# ESP32.net
KiCad netlist of a schematic drawn in Altium Designer
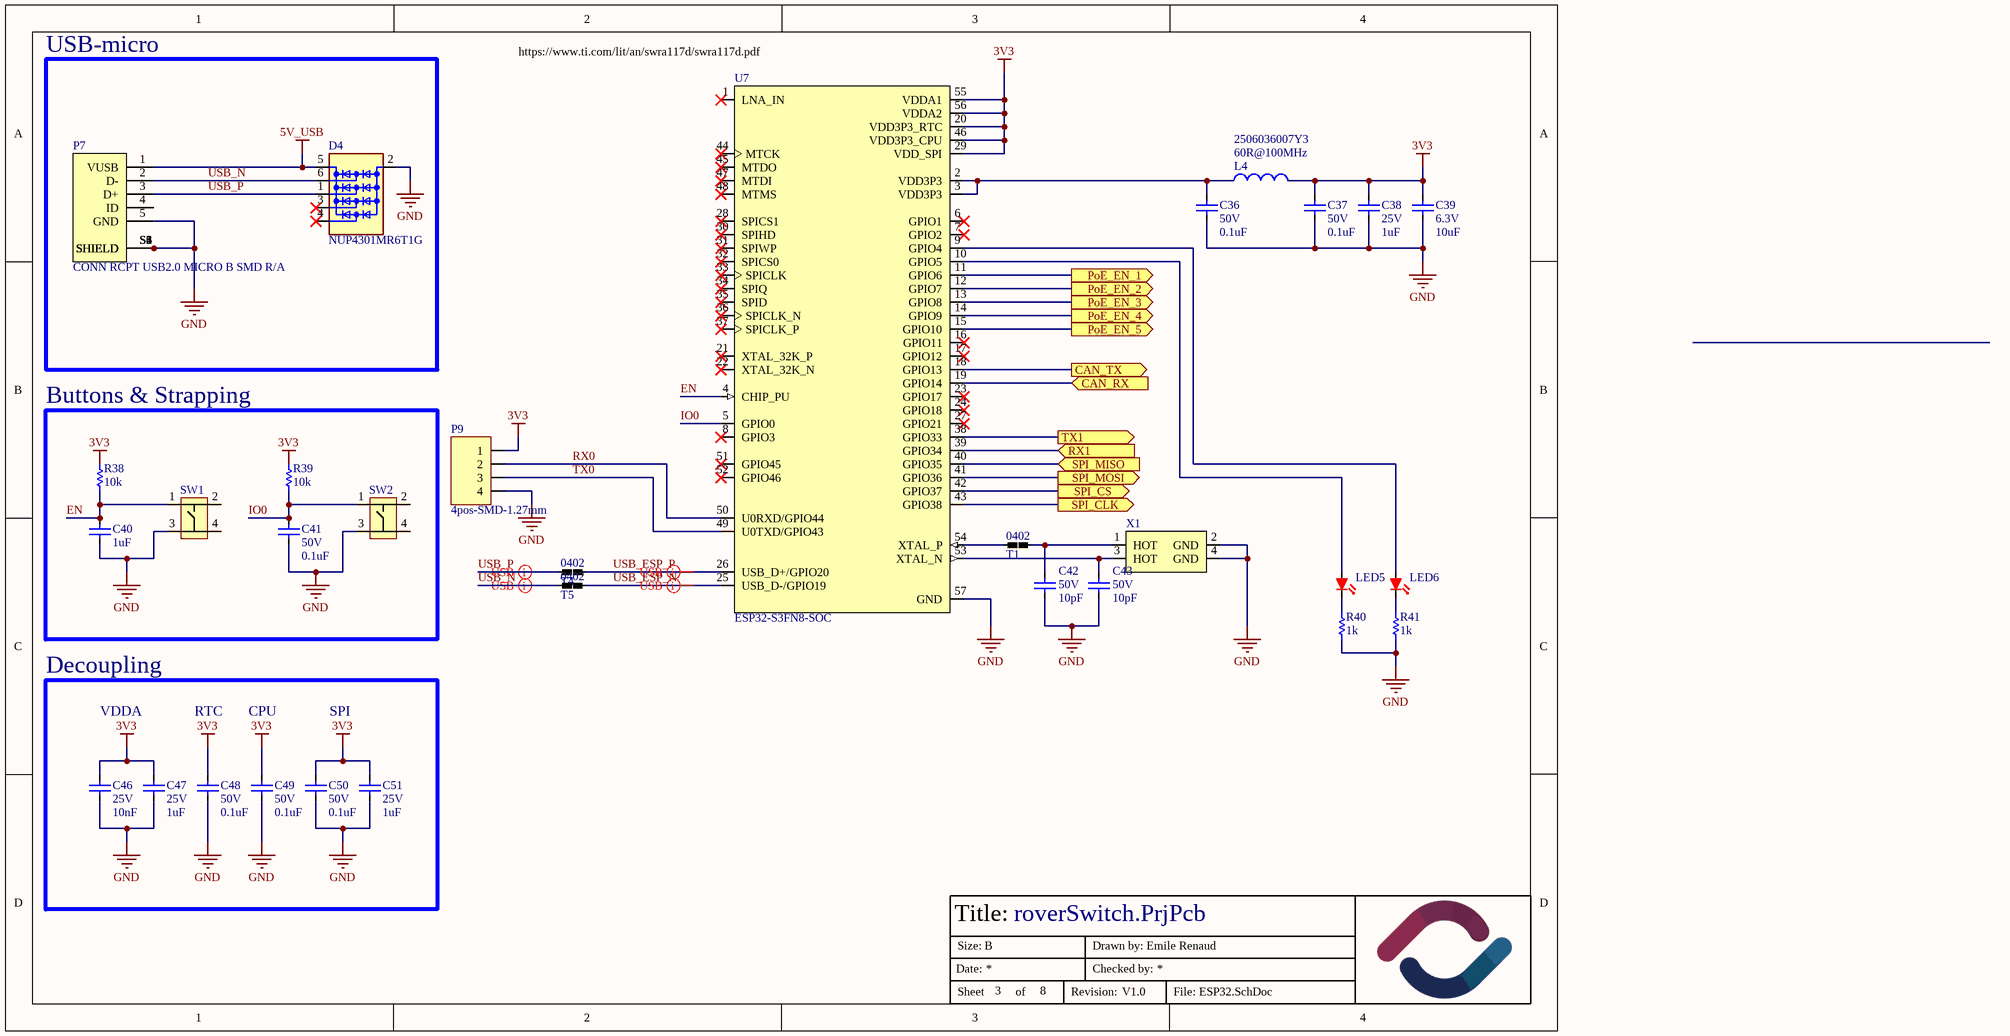
[diagram p0: ESP32.SchDoc]

(export (version "E")
  (design (tool "Eeschema 10.0.6"))
  (components
    (comp (ref "C36")
      (value "0.1uF")
      (footprint "CAPACITOR-0603")
      (description "Capacitor-0603-0.1uF-50V-X7R")
      (fields (field (name "VOLT") "50V"))
      (libsource (lib "Capacitors") (part "Capacitor-0603-0.1uF-50V-X7R"))
    )
    (comp (ref "C37")
      (value "0.1uF")
      (footprint "CAPACITOR-0603")
      (description "Capacitor-0603-0.1uF-50V-X7R")
      (fields (field (name "VOLT") "50V"))
      (libsource (lib "Capacitors") (part "Capacitor-0603-0.1uF-50V-X7R"))
    )
    (comp (ref "C38")
      (value "1uF")
      (footprint "CAPACITOR-0603")
      (description "Capacitor-0603-1uF-25V-X5R")
      (fields (field (name "VOLT") "25V"))
      (libsource (lib "Capacitors") (part "Capacitor-0603-1uF-25V-X5R"))
    )
    (comp (ref "C39")
      (value "10uF")
      (footprint "CAPACITOR-0603")
      (description "Capacitor-0603-10uF-6.3V-X5R, Low ESR, Low ESL")
      (fields (field (name "VOLT") "6.3V") (field (name "Comment") "Capacitor-0603-10uF-6.3V-X5R"))
      (libsource (lib "Capacitors") (part "Capacitor-0603-10uF-6.3V-X5R"))
    )
    (comp (ref "C40")
      (value "1uF")
      (footprint "CAPACITOR-0603")
      (description "Capacitor-0603-1uF-25V-X5R")
      (libsource (lib "Capacitors") (part "Capacitor-0603-1uF-25V-X5R"))
    )
    (comp (ref "C41")
      (value "0.1uF")
      (footprint "CAPACITOR-0603")
      (description "Capacitor-0603-0.1uF-50V-X7R")
      (fields (field (name "VOLT") "50V"))
      (libsource (lib "Capacitors") (part "Capacitor-0603-0.1uF-50V-X7R"))
    )
    (comp (ref "C42")
      (value "10pF")
      (footprint "CAPACITOR-0402")
      (description "Capacitor-0402-10pF-50V-C0G")
      (fields (field (name "VOLT") "50V"))
      (libsource (lib "Capacitors") (part "Capacitor-0402-10pF-50V-C0G"))
    )
    (comp (ref "C43")
      (value "10pF")
      (footprint "CAPACITOR-0402")
      (description "Capacitor-0402-10pF-50V-C0G")
      (fields (field (name "VOLT") "50V"))
      (libsource (lib "Capacitors") (part "Capacitor-0402-10pF-50V-C0G"))
    )
    (comp (ref "C46")
      (value "10nF")
      (footprint "CAPACITOR-0603")
      (description "10000 pF ±10% 25V Ceramic Capacitor X5R 0603 (1608 Metric)")
      (fields (field (name "VOLT") "25V") (field (name "Comment") "Capacitor-0603-10nF-25V-X5R"))
      (libsource (lib "Capacitors") (part "Capacitor-0603-10nF-25V-X5R"))
    )
    (comp (ref "C47")
      (value "1uF")
      (footprint "CAPACITOR-0603")
      (description "Capacitor-0603-1uF-25V-X5R")
      (fields (field (name "VOLT") "25V"))
      (libsource (lib "Capacitors") (part "Capacitor-0603-1uF-25V-X5R"))
    )
    (comp (ref "C48")
      (value "0.1uF")
      (footprint "CAPACITOR-0603")
      (description "Capacitor-0603-0.1uF-50V-X7R")
      (fields (field (name "VOLT") "50V"))
      (libsource (lib "Capacitors") (part "Capacitor-0603-0.1uF-50V-X7R"))
    )
    (comp (ref "C49")
      (value "0.1uF")
      (footprint "CAPACITOR-0603")
      (description "Capacitor-0603-0.1uF-50V-X7R")
      (fields (field (name "VOLT") "50V"))
      (libsource (lib "Capacitors") (part "Capacitor-0603-0.1uF-50V-X7R"))
    )
    (comp (ref "C50")
      (value "0.1uF")
      (footprint "CAPACITOR-0603")
      (description "Capacitor-0603-0.1uF-50V-X7R")
      (fields (field (name "VOLT") "50V"))
      (libsource (lib "Capacitors") (part "Capacitor-0603-0.1uF-50V-X7R"))
    )
    (comp (ref "C51")
      (value "1uF")
      (footprint "CAPACITOR-0603")
      (description "Capacitor-0603-1uF-25V-X5R")
      (fields (field (name "VOLT") "25V"))
      (libsource (lib "Capacitors") (part "Capacitor-0603-1uF-25V-X5R"))
    )
    (comp (ref "D4")
      (value "NUP4301MR6T1G")
      (footprint "SOT-23-6")
      (description "4CH Clamp Ipp Tvs Diode Surface Mount SOT23-6 (SC74)")
      (libsource (lib "diodes") (part "NUP4301MR6T1G"))
    )
    (comp (ref "L4")
      (value "2506036007Y3")
      (footprint "CAPACITOR-0603")
      (description "60 Ohms @ 100 MHz 1 Signal Line Ferrite Bead 0603 (1608 Metric) 3A 40mOhm")
      (fields (field (name "ALTIUM_VALUE") "60R@100MHz"))
      (libsource (lib "Inductors") (part "2506036007Y3"))
    )
    (comp (ref "LED5")
      (value "B1911USD-20D000114U1930")
      (footprint "LED-0603-2PIN")
      (description "LED RED CLEAR 1608 SMD")
      (libsource (lib "LEDs") (part "B1911USD-20D000114U1930"))
    )
    (comp (ref "LED6")
      (value "B1911USD-20D000114U1930")
      (footprint "LED-0603-2PIN")
      (description "LED RED CLEAR 1608 SMD")
      (libsource (lib "LEDs") (part "B1911USD-20D000114U1930"))
    )
    (comp (ref "P7")
      (value "CONN RCPT USB2.0 MICRO B SMD R/A")
      (footprint "FCI_10118193-0001LF")
      (description "USB - micro B USB 2.0 Receptacle Connector 5 Position Surface Mount, Right Angle; Through Hole")
      (libsource (lib "PC-connector") (part "USB-Micro"))
    )
    (comp (ref "P9")
      (value "4pos-SMD-1.27mm")
      (footprint "HDR1X4-SMD-50mils")
      (description "4pos SMD 1.27mm")
      (libsource (lib "Header") (part "4pos-SMD-1.27mm"))
    )
    (comp (ref "R38")
      (value "10k")
      (footprint "Resistor-0603")
      (description "Resistor0603-10k")
      (fields (field (name "Comment") "SMT resistor"))
      (libsource (lib "Resistors") (part "Resistor0603-10k"))
    )
    (comp (ref "R39")
      (value "10k")
      (footprint "Resistor-0603")
      (description "Resistor0603-10k")
      (fields (field (name "Comment") "SMT resistor"))
      (libsource (lib "Resistors") (part "Resistor0603-10k"))
    )
    (comp (ref "R40")
      (value "1k")
      (footprint "Resistor-0603")
      (description "Resistor0603-1k")
      (fields (field (name "Comment") "SMT resistor"))
      (libsource (lib "Resistors") (part "Resistor-0603-1k"))
    )
    (comp (ref "R41")
      (value "1k")
      (footprint "Resistor-0603")
      (description "Resistor0603-1k")
      (fields (field (name "Comment") "SMT resistor"))
      (libsource (lib "Resistors") (part "Resistor-0603-1k"))
    )
    (comp (ref "SW1")
      (value "PTS815 SJM 250 SMTR LFS")
      (footprint "SW4_PTS815 SJM 250 SMTR LFS_CNK")
      (description "TACT 4.2 X 3.2, 2.5 MM H, 180GF,")
      (libsource (lib "THTPushButtonSwitches") (part "PTS815 SJM 250 SMTR LFS"))
    )
    (comp (ref "SW2")
      (value "PTS815 SJM 250 SMTR LFS")
      (footprint "SW4_PTS815 SJM 250 SMTR LFS_CNK")
      (description "TACT 4.2 X 3.2, 2.5 MM H, 180GF,")
      (libsource (lib "THTPushButtonSwitches") (part "PTS815 SJM 250 SMTR LFS"))
    )
    (comp (ref "T1")
      (value "NetTie_0402")
      (footprint "NetTie-0402")
      (libsource (lib "JumpersAndHoles") (part "NetTie_0402"))
    )
    (comp (ref "T4")
      (value "NetTie_0402")
      (footprint "NetTie-0402")
      (libsource (lib "JumpersAndHoles") (part "NetTie_0402"))
    )
    (comp (ref "T5")
      (value "NetTie_0402")
      (footprint "NetTie-0402")
      (libsource (lib "JumpersAndHoles") (part "NetTie_0402"))
    )
    (comp (ref "U7")
      (value "ESP32-S3FN8-SOC")
      (footprint "VFQFN-56 Exposed Pad")
      (fields (field (name "MF") "Espressif Systems") (field (name "MP") "ESP32-S3FN8"))
      (libsource (lib "Microcontrollers") (part "ESP32-S3FN8-SOC"))
    )
    (comp (ref "X1")
      (value "CX2016DB40000D0FLJCC")
      (footprint "4-SMD")
      (description "40 MHz ±10ppm Crystal 8pF 50 Ohms 4-SMD, No Lead")
      (libsource (lib "Crystals") (part "CX2016DB40000D0FLJCC"))
    )
  )
  (nets
    (net (code "1") (name "/CAN_RX") (class "Default")
      (node (ref "U7") (pin "19") (pinfunction "GPIO14_19") (pintype "bidirectional"))
    )
    (net (code "2") (name "/CAN_TX") (class "Default")
      (node (ref "U7") (pin "18") (pinfunction "GPIO13_18") (pintype "bidirectional"))
    )
    (net (code "3") (name "/EN") (class "Default")
      (node (ref "C40") (pin "2") (pinfunction "2_2") (pintype "passive"))
      (node (ref "R38") (pin "1") (pinfunction "1_1") (pintype "passive"))
      (node (ref "SW1") (pin "1") (pinfunction "1_1") (pintype "passive"))
      (node (ref "U7") (pin "4") (pinfunction "CHIP_PU_4") (pintype "input"))
    )
    (net (code "4") (name "/IO0") (class "Default")
      (node (ref "C41") (pin "2") (pinfunction "2_2") (pintype "passive"))
      (node (ref "R39") (pin "1") (pinfunction "1_1") (pintype "passive"))
      (node (ref "SW2") (pin "1") (pinfunction "1_1") (pintype "passive"))
      (node (ref "U7") (pin "5") (pinfunction "GPIO0_5") (pintype "bidirectional"))
    )
    (net (code "5") (name "/PoE_EN_1") (class "Default")
      (node (ref "U7") (pin "11") (pinfunction "GPIO6_11") (pintype "bidirectional"))
    )
    (net (code "6") (name "/PoE_EN_2") (class "Default")
      (node (ref "U7") (pin "12") (pinfunction "GPIO7_12") (pintype "bidirectional"))
    )
    (net (code "7") (name "/PoE_EN_3") (class "Default")
      (node (ref "U7") (pin "13") (pinfunction "GPIO8_13") (pintype "bidirectional"))
    )
    (net (code "8") (name "/PoE_EN_4") (class "Default")
      (node (ref "U7") (pin "14") (pinfunction "GPIO9_14") (pintype "bidirectional"))
    )
    (net (code "9") (name "/PoE_EN_5") (class "Default")
      (node (ref "U7") (pin "15") (pinfunction "GPIO10_15") (pintype "bidirectional"))
    )
    (net (code "10") (name "/RX0") (class "Default")
      (node (ref "P9") (pin "2") (pinfunction "2_2") (pintype "passive"))
      (node (ref "U7") (pin "50") (pinfunction "U0RXD/GPIO44_50") (pintype "bidirectional"))
    )
    (net (code "11") (name "/RX1") (class "Default")
      (node (ref "U7") (pin "39") (pinfunction "GPIO34_39") (pintype "bidirectional"))
    )
    (net (code "12") (name "/SPI_CLK") (class "Default")
      (node (ref "U7") (pin "43") (pinfunction "GPIO38_43") (pintype "bidirectional"))
    )
    (net (code "13") (name "/SPI_CS") (class "Default")
      (node (ref "U7") (pin "42") (pinfunction "GPIO37_42") (pintype "bidirectional"))
    )
    (net (code "14") (name "/SPI_MISO") (class "Default")
      (node (ref "U7") (pin "40") (pinfunction "GPIO35_40") (pintype "bidirectional"))
    )
    (net (code "15") (name "/SPI_MOSI") (class "Default")
      (node (ref "U7") (pin "41") (pinfunction "GPIO36_41") (pintype "bidirectional"))
    )
    (net (code "16") (name "/TX0") (class "Default")
      (node (ref "P9") (pin "3") (pinfunction "3_3") (pintype "passive"))
      (node (ref "U7") (pin "49") (pinfunction "U0TXD/GPIO43_49") (pintype "bidirectional"))
    )
    (net (code "17") (name "/TX1") (class "Default")
      (node (ref "U7") (pin "38") (pinfunction "GPIO33_38") (pintype "bidirectional"))
    )
    (net (code "18") (name "/USB_ESP_N") (class "Default")
      (node (ref "T5") (pin "1") (pinfunction "1_1") (pintype "passive"))
      (node (ref "U7") (pin "25") (pinfunction "USB_D-/GPIO19_25") (pintype "bidirectional"))
    )
    (net (code "19") (name "/USB_ESP_P") (class "Default")
      (node (ref "T4") (pin "1") (pinfunction "1_1") (pintype "passive"))
      (node (ref "U7") (pin "26") (pinfunction "USB_D+/GPIO20_26") (pintype "bidirectional"))
    )
    (net (code "20") (name "/USB_N") (class "Default")
      (node (ref "D4") (pin "6") (pinfunction "L1_6") (pintype "passive"))
      (node (ref "P7") (pin "2") (pinfunction "D-_2") (pintype "passive"))
      (node (ref "T5") (pin "2") (pinfunction "2_2") (pintype "passive"))
    )
    (net (code "21") (name "/USB_P") (class "Default")
      (node (ref "D4") (pin "1") (pinfunction "L2_1") (pintype "passive"))
      (node (ref "P7") (pin "3") (pinfunction "D+_3") (pintype "passive"))
      (node (ref "T4") (pin "2") (pinfunction "2_2") (pintype "passive"))
    )
    (net (code "22") (name "3V3") (class "Default")
      (node (ref "C37") (pin "2") (pinfunction "2_2") (pintype "passive"))
      (node (ref "C38") (pin "2") (pinfunction "2_2") (pintype "passive"))
      (node (ref "C39") (pin "2") (pinfunction "2_2") (pintype "passive"))
      (node (ref "C46") (pin "2") (pinfunction "2_2") (pintype "passive"))
      (node (ref "C47") (pin "2") (pinfunction "2_2") (pintype "passive"))
      (node (ref "C48") (pin "2") (pinfunction "2_2") (pintype "passive"))
      (node (ref "C49") (pin "2") (pinfunction "2_2") (pintype "passive"))
      (node (ref "C50") (pin "2") (pinfunction "2_2") (pintype "passive"))
      (node (ref "C51") (pin "2") (pinfunction "2_2") (pintype "passive"))
      (node (ref "L4") (pin "2") (pinfunction "2_2") (pintype "passive"))
      (node (ref "P9") (pin "1") (pinfunction "1_1") (pintype "passive"))
      (node (ref "R38") (pin "2") (pinfunction "2_2") (pintype "passive"))
      (node (ref "R39") (pin "2") (pinfunction "2_2") (pintype "passive"))
      (node (ref "U7") (pin "20") (pinfunction "VDD3P3_RTC_20") (pintype "power_in"))
      (node (ref "U7") (pin "29") (pinfunction "VDD_SPI_29") (pintype "power_in"))
      (node (ref "U7") (pin "46") (pinfunction "VDD3P3_CPU_46") (pintype "power_in"))
      (node (ref "U7") (pin "55") (pinfunction "VDDA1_55") (pintype "power_in"))
      (node (ref "U7") (pin "56") (pinfunction "VDDA2_56") (pintype "power_in"))
    )
    (net (code "23") (name "5V_USB") (class "Default")
      (node (ref "D4") (pin "5") (pinfunction "VDD_5") (pintype "passive"))
      (node (ref "P7") (pin "1") (pinfunction "VUSB_1") (pintype "passive"))
    )
    (net (code "24") (name "GND") (class "Default")
      (node (ref "C36") (pin "1") (pinfunction "1_1") (pintype "passive"))
      (node (ref "C37") (pin "1") (pinfunction "1_1") (pintype "passive"))
      (node (ref "C38") (pin "1") (pinfunction "1_1") (pintype "passive"))
      (node (ref "C39") (pin "1") (pinfunction "1_1") (pintype "passive"))
      (node (ref "C40") (pin "1") (pinfunction "1_1") (pintype "passive"))
      (node (ref "C41") (pin "1") (pinfunction "1_1") (pintype "passive"))
      (node (ref "C42") (pin "1") (pinfunction "1_1") (pintype "passive"))
      (node (ref "C43") (pin "1") (pinfunction "1_1") (pintype "passive"))
      (node (ref "C46") (pin "1") (pinfunction "1_1") (pintype "passive"))
      (node (ref "C47") (pin "1") (pinfunction "1_1") (pintype "passive"))
      (node (ref "C48") (pin "1") (pinfunction "1_1") (pintype "passive"))
      (node (ref "C49") (pin "1") (pinfunction "1_1") (pintype "passive"))
      (node (ref "C50") (pin "1") (pinfunction "1_1") (pintype "passive"))
      (node (ref "C51") (pin "1") (pinfunction "1_1") (pintype "passive"))
      (node (ref "D4") (pin "2") (pinfunction "GND_2") (pintype "passive"))
      (node (ref "P7") (pin "5") (pinfunction "GND_5") (pintype "passive"))
      (node (ref "P7") (pin "S1") (pinfunction "SHIELD_S1") (pintype "passive"))
      (node (ref "P7") (pin "S2") (pinfunction "SHIELD_S2") (pintype "passive"))
      (node (ref "P7") (pin "S3") (pinfunction "SHIELD_S3") (pintype "passive"))
      (node (ref "P7") (pin "S4") (pinfunction "SHIELD_S4") (pintype "passive"))
      (node (ref "P7") (pin "S5") (pinfunction "SHIELD_S5") (pintype "passive"))
      (node (ref "P7") (pin "S6") (pinfunction "SHIELD_S6") (pintype "passive"))
      (node (ref "P9") (pin "4") (pinfunction "4_4") (pintype "passive"))
      (node (ref "R40") (pin "1") (pinfunction "1_1") (pintype "passive"))
      (node (ref "R41") (pin "1") (pinfunction "1_1") (pintype "passive"))
      (node (ref "SW1") (pin "3") (pinfunction "3_3") (pintype "passive"))
      (node (ref "SW2") (pin "3") (pinfunction "3_3") (pintype "passive"))
      (node (ref "U7") (pin "57") (pinfunction "GND_57") (pintype "power_in"))
      (node (ref "X1") (pin "2") (pinfunction "GND_2") (pintype "passive"))
      (node (ref "X1") (pin "4") (pinfunction "GND_4") (pintype "passive"))
    )
    (net (code "25") (name "Net-(C36-Pad2)") (class "Default")
      (node (ref "C36") (pin "2") (pinfunction "2_2") (pintype "passive"))
      (node (ref "L4") (pin "1") (pinfunction "1_1") (pintype "passive"))
      (node (ref "U7") (pin "2") (pinfunction "VDD3P3_2") (pintype "power_in"))
      (node (ref "U7") (pin "3") (pinfunction "VDD3P3_3") (pintype "power_in"))
    )
    (net (code "26") (name "Net-(C42-Pad2)") (class "Default")
      (node (ref "C42") (pin "2") (pinfunction "2_2") (pintype "passive"))
      (node (ref "T1") (pin "1") (pinfunction "1_1") (pintype "passive"))
      (node (ref "X1") (pin "1") (pinfunction "HOT_1") (pintype "passive"))
    )
    (net (code "27") (name "Net-(LED5-K)") (class "Default")
      (node (ref "LED5") (pin "1") (pinfunction "K_1") (pintype "passive"))
      (node (ref "R40") (pin "2") (pinfunction "2_2") (pintype "passive"))
    )
    (net (code "28") (name "Net-(LED5-R)") (class "Default")
      (node (ref "LED5") (pin "2") (pinfunction "R_2") (pintype "passive"))
      (node (ref "U7") (pin "10") (pinfunction "GPIO5_10") (pintype "bidirectional"))
    )
    (net (code "29") (name "Net-(LED6-K)") (class "Default")
      (node (ref "LED6") (pin "1") (pinfunction "K_1") (pintype "passive"))
      (node (ref "R41") (pin "2") (pinfunction "2_2") (pintype "passive"))
    )
    (net (code "30") (name "Net-(LED6-R)") (class "Default")
      (node (ref "LED6") (pin "2") (pinfunction "R_2") (pintype "passive"))
      (node (ref "U7") (pin "9") (pinfunction "GPIO4_9") (pintype "bidirectional"))
    )
    (net (code "31") (name "Net-(U7-XTAL_N)") (class "Default")
      (node (ref "C43") (pin "2") (pinfunction "2_2") (pintype "passive"))
      (node (ref "U7") (pin "53") (pinfunction "XTAL_N_53") (pintype "output"))
      (node (ref "X1") (pin "3") (pinfunction "HOT_3") (pintype "passive"))
    )
    (net (code "32") (name "Net-(U7-XTAL_P)") (class "Default")
      (node (ref "T1") (pin "2") (pinfunction "2_2") (pintype "passive"))
      (node (ref "U7") (pin "54") (pinfunction "XTAL_P_54") (pintype "input"))
    )
    (net (code "33") (name "unconnected-(D4-L3-Pad3)") (class "Default")
      (node (ref "D4") (pin "3") (pinfunction "L3_3") (pintype "passive+no_connect"))
    )
    (net (code "34") (name "unconnected-(D4-L4-Pad4)") (class "Default")
      (node (ref "D4") (pin "4") (pinfunction "L4_4") (pintype "passive+no_connect"))
    )
    (net (code "35") (name "unconnected-(P7-ID-Pad4)") (class "Default")
      (node (ref "P7") (pin "4") (pinfunction "ID_4") (pintype "passive"))
    )
    (net (code "36") (name "unconnected-(SW1-Pad2)") (class "Default")
      (node (ref "SW1") (pin "2") (pinfunction "2_2") (pintype "passive"))
    )
    (net (code "37") (name "unconnected-(SW1-Pad4)") (class "Default")
      (node (ref "SW1") (pin "4") (pinfunction "4_4") (pintype "passive"))
    )
    (net (code "38") (name "unconnected-(SW2-Pad2)") (class "Default")
      (node (ref "SW2") (pin "2") (pinfunction "2_2") (pintype "passive"))
    )
    (net (code "39") (name "unconnected-(SW2-Pad4)") (class "Default")
      (node (ref "SW2") (pin "4") (pinfunction "4_4") (pintype "passive"))
    )
    (net (code "40") (name "unconnected-(U7-GPIO1-Pad6)") (class "Default")
      (node (ref "U7") (pin "6") (pinfunction "GPIO1_6") (pintype "bidirectional+no_connect"))
    )
    (net (code "41") (name "unconnected-(U7-GPIO2-Pad7)") (class "Default")
      (node (ref "U7") (pin "7") (pinfunction "GPIO2_7") (pintype "bidirectional+no_connect"))
    )
    (net (code "42") (name "unconnected-(U7-GPIO3-Pad8)") (class "Default")
      (node (ref "U7") (pin "8") (pinfunction "GPIO3_8") (pintype "bidirectional+no_connect"))
    )
    (net (code "43") (name "unconnected-(U7-GPIO11-Pad16)") (class "Default")
      (node (ref "U7") (pin "16") (pinfunction "GPIO11_16") (pintype "bidirectional+no_connect"))
    )
    (net (code "44") (name "unconnected-(U7-GPIO12-Pad17)") (class "Default")
      (node (ref "U7") (pin "17") (pinfunction "GPIO12_17") (pintype "bidirectional+no_connect"))
    )
    (net (code "45") (name "unconnected-(U7-GPIO17-Pad23)") (class "Default")
      (node (ref "U7") (pin "23") (pinfunction "GPIO17_23") (pintype "bidirectional+no_connect"))
    )
    (net (code "46") (name "unconnected-(U7-GPIO18-Pad24)") (class "Default")
      (node (ref "U7") (pin "24") (pinfunction "GPIO18_24") (pintype "bidirectional+no_connect"))
    )
    (net (code "47") (name "unconnected-(U7-GPIO21-Pad27)") (class "Default")
      (node (ref "U7") (pin "27") (pinfunction "GPIO21_27") (pintype "bidirectional+no_connect"))
    )
    (net (code "48") (name "unconnected-(U7-GPIO45-Pad51)") (class "Default")
      (node (ref "U7") (pin "51") (pinfunction "GPIO45_51") (pintype "bidirectional+no_connect"))
    )
    (net (code "49") (name "unconnected-(U7-GPIO46-Pad52)") (class "Default")
      (node (ref "U7") (pin "52") (pinfunction "GPIO46_52") (pintype "bidirectional+no_connect"))
    )
    (net (code "50") (name "unconnected-(U7-LNA_IN-Pad1)") (class "Default")
      (node (ref "U7") (pin "1") (pinfunction "LNA_IN_1") (pintype "bidirectional+no_connect"))
    )
    (net (code "51") (name "unconnected-(U7-MTCK-Pad44)") (class "Default")
      (node (ref "U7") (pin "44") (pinfunction "MTCK_44") (pintype "bidirectional+no_connect"))
    )
    (net (code "52") (name "unconnected-(U7-MTDI-Pad47)") (class "Default")
      (node (ref "U7") (pin "47") (pinfunction "MTDI_47") (pintype "bidirectional+no_connect"))
    )
    (net (code "53") (name "unconnected-(U7-MTDO-Pad45)") (class "Default")
      (node (ref "U7") (pin "45") (pinfunction "MTDO_45") (pintype "bidirectional+no_connect"))
    )
    (net (code "54") (name "unconnected-(U7-MTMS-Pad48)") (class "Default")
      (node (ref "U7") (pin "48") (pinfunction "MTMS_48") (pintype "bidirectional+no_connect"))
    )
    (net (code "55") (name "unconnected-(U7-SPICLK-Pad33)") (class "Default")
      (node (ref "U7") (pin "33") (pinfunction "SPICLK_33") (pintype "bidirectional+no_connect"))
    )
    (net (code "56") (name "unconnected-(U7-SPICLK_N-Pad36)") (class "Default")
      (node (ref "U7") (pin "36") (pinfunction "SPICLK_N_36") (pintype "bidirectional+no_connect"))
    )
    (net (code "57") (name "unconnected-(U7-SPICLK_P-Pad37)") (class "Default")
      (node (ref "U7") (pin "37") (pinfunction "SPICLK_P_37") (pintype "bidirectional+no_connect"))
    )
    (net (code "58") (name "unconnected-(U7-SPICS0-Pad32)") (class "Default")
      (node (ref "U7") (pin "32") (pinfunction "SPICS0_32") (pintype "bidirectional+no_connect"))
    )
    (net (code "59") (name "unconnected-(U7-SPICS1-Pad28)") (class "Default")
      (node (ref "U7") (pin "28") (pinfunction "SPICS1_28") (pintype "bidirectional+no_connect"))
    )
    (net (code "60") (name "unconnected-(U7-SPID-Pad35)") (class "Default")
      (node (ref "U7") (pin "35") (pinfunction "SPID_35") (pintype "bidirectional+no_connect"))
    )
    (net (code "61") (name "unconnected-(U7-SPIHD-Pad30)") (class "Default")
      (node (ref "U7") (pin "30") (pinfunction "SPIHD_30") (pintype "bidirectional+no_connect"))
    )
    (net (code "62") (name "unconnected-(U7-SPIQ-Pad34)") (class "Default")
      (node (ref "U7") (pin "34") (pinfunction "SPIQ_34") (pintype "bidirectional+no_connect"))
    )
    (net (code "63") (name "unconnected-(U7-SPIWP-Pad31)") (class "Default")
      (node (ref "U7") (pin "31") (pinfunction "SPIWP_31") (pintype "bidirectional+no_connect"))
    )
    (net (code "64") (name "unconnected-(U7-XTAL_32K_N-Pad22)") (class "Default")
      (node (ref "U7") (pin "22") (pinfunction "XTAL_32K_N_22") (pintype "bidirectional+no_connect"))
    )
    (net (code "65") (name "unconnected-(U7-XTAL_32K_P-Pad21)") (class "Default")
      (node (ref "U7") (pin "21") (pinfunction "XTAL_32K_P_21") (pintype "bidirectional+no_connect"))
    )
  )
)
